# top.net
KiCad netlist of a schematic drawn in Altium Designer
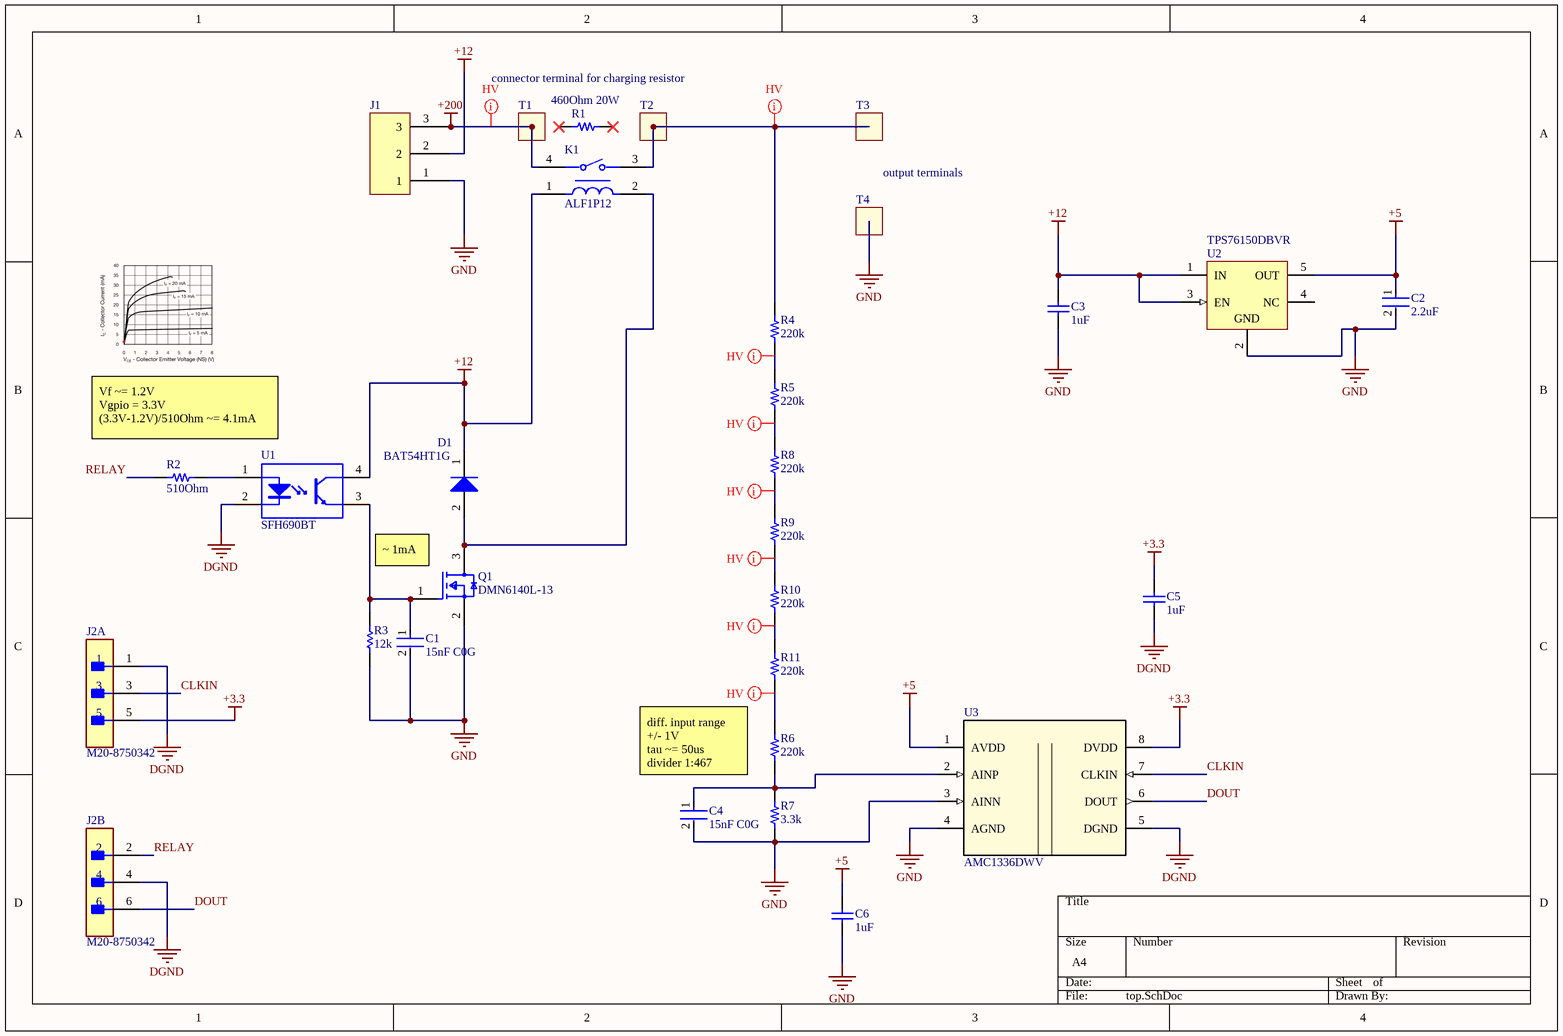
[diagram p0: top.SchDoc]

(export (version "E")
  (design (tool "Eeschema 10.0.6"))
  (components
    (comp (ref "C1")
      (value "15nF C0G")
      (footprint "FP-C0603C-CF-MFG")
      (description "C0603 15,000 pF C0G 30ppm/°C 20.00% 25 V")
      (fields
        (field (name "MANUFACTURER PART NUMBER") "C0603C153M3GACTU")
        (field (name "MANUFACTURER") "KEMET")
      )
      (libsource (lib "Altium Content Vault") (part "b4654b650e69147ec39a6b967a45e02"))
    )
    (comp (ref "C2")
      (value "2.2uF")
      (footprint "FP-GRM188-0_1-e0_2_0_5-MFG")
      (description "Chip Multilayer Ceramic Capacitors for General Purpose, 0603, 2.2uF, X7R, 15%, 10%, 10V")
      (fields (field (name "VOLTAGE") "10V") (field (name "TOLERANCE") "10%"))
      (libsource (lib "Altium Content Vault") (part "11868f565c42a9108669ba33697ecf6"))
    )
    (comp (ref "C3")
      (value "1uF")
      (footprint "CAPC1608X87X35LL15T15")
      (fields (field (name "PART NUMBER") "C0603C105K3RACTU") (field (name "MANUFACTURER") "Kemet"))
      (libsource (lib "Altium Content Vault") (part "CAP"))
    )
    (comp (ref "C4")
      (value "15nF C0G")
      (footprint "FP-C0603C-CF-MFG")
      (description "C0603 15,000 pF C0G 30ppm/°C 20.00% 25 V")
      (fields
        (field (name "MANUFACTURER PART NUMBER") "C0603C153M3GACTU")
        (field (name "MANUFACTURER") "KEMET")
      )
      (libsource (lib "Altium Content Vault") (part "b4654b650e69147ec39a6b967a45e02"))
    )
    (comp (ref "C5")
      (value "1uF")
      (footprint "CAPC1608X87X35LL15T15")
      (fields (field (name "PART NUMBER") "C0603C105K3RACTU") (field (name "MANUFACTURER") "Kemet"))
      (libsource (lib "Altium Content Vault") (part "CAP"))
    )
    (comp (ref "C6")
      (value "1uF")
      (footprint "CAPC1608X87X35LL15T15")
      (fields (field (name "PART NUMBER") "C0603C105K3RACTU") (field (name "MANUFACTURER") "Kemet"))
      (libsource (lib "Altium Content Vault") (part "CAP"))
    )
    (comp (ref "D1")
      (value "BAT54HT1G")
      (footprint "ONSC-SOD-323-2-477-02_V")
      (description "Schottky Barrier Diode, 2-Pin SOD-323, Pb-Free, Tape and Reel")
      (fields (field (name "MANUFACTURER") "On Semiconductor"))
      (libsource (lib "Altium Content Vault") (part "ONSC-D-K1A2-2"))
    )
    (comp (ref "J1")
      (value "20A Socket 3Pin")
      (footprint "weidmuller_3p_20A")
      (libsource (lib "coil_driver_lib") (part "wuerth_connector_straight_30_20A_691311500103"))
    )
    (comp (ref "J2")
      (value "M20-8750342")
      (footprint "FP-M20-8750342-MFG")
      (description "CONN HEADER SMD 6POS 2.54MM")
      (libsource (lib "Altium Content Vault") (part "2654a11fb13586ecb194516b1c997bc"))
    )
    (comp (ref "K1")
      (value "ALF1P12")
      (footprint "FP-ALF1P12-MFG")
      (description "RELAY GEN PURPOSE SPST 20A 12V")
      (libsource (lib "Altium Content Vault") (part "80a4a68f91ad243dcae29d2df2c1dea"))
    )
    (comp (ref "Q1")
      (value "DMN6140L-13")
      (footprint "FP-SOT23-MFG")
      (description "MOSFET N-CH 60V 1.6A SOT23")
      (fields
        (field (name "OCTOPART") "https://octopart.com/dmn6140l-13-diodes+inc.-38898616")
        (field (name "MANUFACTURER") "Diodes Inc.")
      )
      (libsource (lib "Altium Content Vault") (part "0a9ea7c96deaaede766a5b531c28de0"))
    )
    (comp (ref "R1")
      (value "460Ohm 20W")
      (description "SMT Resistor")
      (libsource (lib "SCH - PASSIVES - RESISTOR") (part "Resistor"))
    )
    (comp (ref "R2")
      (value "510Ohm")
      (footprint "RES 0603_1608")
      (description "SMT Resistor")
      (libsource (lib "SCH - PASSIVES - RESISTOR") (part "Resistor"))
    )
    (comp (ref "R3")
      (value "12k")
      (footprint "RES 0805_2012")
      (description "Resistor")
      (fields (field (name "PUBLISHER") "Altium Limited"))
      (libsource (lib "Miscellaneous Devices") (part "Res1"))
    )
    (comp (ref "R4")
      (value "220k")
      (footprint "RES 0603_1608 RF")
      (description "SMT Resistor")
      (libsource (lib "SCH - PASSIVES - RESISTOR") (part "Resistor"))
    )
    (comp (ref "R5")
      (value "220k")
      (footprint "RES 0603_1608 RF")
      (description "SMT Resistor")
      (libsource (lib "SCH - PASSIVES - RESISTOR") (part "Resistor"))
    )
    (comp (ref "R6")
      (value "220k")
      (footprint "RES 0603_1608 RF")
      (description "SMT Resistor")
      (libsource (lib "SCH - PASSIVES - RESISTOR") (part "Resistor"))
    )
    (comp (ref "R7")
      (value "3.3k")
      (footprint "RES 0603_1608")
      (description "SMT Resistor")
      (libsource (lib "SCH - PASSIVES - RESISTOR") (part "Resistor"))
    )
    (comp (ref "R8")
      (value "220k")
      (footprint "RES 0603_1608 RF")
      (description "SMT Resistor")
      (libsource (lib "SCH - PASSIVES - RESISTOR") (part "Resistor"))
    )
    (comp (ref "R9")
      (value "220k")
      (footprint "RES 0603_1608 RF")
      (description "SMT Resistor")
      (libsource (lib "SCH - PASSIVES - RESISTOR") (part "Resistor"))
    )
    (comp (ref "R10")
      (value "220k")
      (footprint "RES 0603_1608 RF")
      (description "SMT Resistor")
      (libsource (lib "SCH - PASSIVES - RESISTOR") (part "Resistor"))
    )
    (comp (ref "R11")
      (value "220k")
      (footprint "RES 0603_1608 RF")
      (description "SMT Resistor")
      (libsource (lib "SCH - PASSIVES - RESISTOR") (part "Resistor"))
    )
    (comp (ref "T1")
      (value "pwr_connector_quick")
      (footprint "pcb_quick_power_connector")
      (libsource (lib "coil_driver_lib") (part "pwr_connector_quick"))
    )
    (comp (ref "T2")
      (value "pwr_connector_quick")
      (footprint "pcb_quick_power_connector")
      (libsource (lib "coil_driver_lib") (part "pwr_connector_quick"))
    )
    (comp (ref "T3")
      (value "pwr_connector_quick")
      (footprint "pcb_quick_power_connector")
      (libsource (lib "coil_driver_lib") (part "pwr_connector_quick"))
    )
    (comp (ref "T4")
      (value "pwr_connector_quick")
      (footprint "pcb_quick_power_connector")
      (libsource (lib "coil_driver_lib") (part "pwr_connector_quick"))
    )
    (comp (ref "U1")
      (value "SFH690BT")
      (footprint "VISH-SOP-4_A_V")
      (description "Optocoupler Phototransistor Output, 6 V, 50 mA, -55 to 100 degC, 4-Pin SOIC, RoHS, Tape and Reel")
      (fields (field (name "MANUFACTURER") "Vishay"))
      (libsource (lib "Altium Content Vault") (part "OPTO-AKEC-4"))
    )
    (comp (ref "U2")
      (value "TPS76150DBVR")
      (footprint "DBV0005A_M")
      (fields (field (name "MANUFACTURER") "Texas Instruments"))
      (libsource (lib "Altium Content Vault") (part "TI-TXX7XXXX-5"))
    )
    (comp (ref "U3")
      (value "AMC1336DWV")
      (footprint "AMC1336")
      (description "&plusmn;1-V input, precision voltage sensing reinforced isolated modulator 8-SOIC -40 to 125")
      (fields (field (name "COPYRIGHT") "Copyright (C) 2025 Ultra Librarian. All rights reserved."))
      (libsource (lib "AMC1336DWV") (part "AMC1336DWV"))
    )
  )
  (nets
    (net (code "1") (name "+3.3") (class "Default")
      (node (ref "C5") (pin "2") (pinfunction "2_2") (pintype "passive"))
      (node (ref "J2") (pin "5") (pinfunction "5_5") (pintype "passive"))
      (node (ref "U3") (pin "8") (pinfunction "DVDD_8") (pintype "power_in"))
    )
    (net (code "2") (name "+5") (class "Default")
      (node (ref "C2") (pin "1") (pinfunction "1_1") (pintype "passive"))
      (node (ref "C6") (pin "2") (pinfunction "2_2") (pintype "passive"))
      (node (ref "U2") (pin "5") (pinfunction "OUT_5") (pintype "power_in"))
      (node (ref "U3") (pin "1") (pinfunction "AVDD_1") (pintype "power_in"))
    )
    (net (code "3") (name "+12") (class "Default")
      (node (ref "C3") (pin "2") (pinfunction "2_2") (pintype "passive"))
      (node (ref "D1") (pin "1") (pinfunction "K_1") (pintype "passive"))
      (node (ref "J1") (pin "2") (pinfunction "2_2") (pintype "passive"))
      (node (ref "K1") (pin "1") (pinfunction "1_1") (pintype "passive"))
      (node (ref "U1") (pin "4") (pinfunction "COLLECTOR_4") (pintype "passive"))
      (node (ref "U2") (pin "1") (pinfunction "IN_1") (pintype "power_in"))
      (node (ref "U2") (pin "3") (pinfunction "EN_3") (pintype "input"))
    )
    (net (code "4") (name "+200") (class "Default")
      (node (ref "J1") (pin "3") (pinfunction "3_3") (pintype "passive"))
      (node (ref "K1") (pin "4") (pinfunction "COM_4") (pintype "passive"))
      (node (ref "T1") (pin "1") (pinfunction "1_1") (pintype "passive"))
    )
    (net (code "5") (name "/CLKIN") (class "Default")
      (node (ref "J2") (pin "3") (pinfunction "3_3") (pintype "passive"))
      (node (ref "U3") (pin "7") (pinfunction "CLKIN_7") (pintype "input"))
    )
    (net (code "6") (name "/DOUT") (class "Default")
      (node (ref "J2") (pin "6") (pinfunction "6_6") (pintype "passive"))
      (node (ref "U3") (pin "6") (pinfunction "DOUT_6") (pintype "output"))
    )
    (net (code "7") (name "/RELAY") (class "Default")
      (node (ref "J2") (pin "2") (pinfunction "2_2") (pintype "passive"))
      (node (ref "R2") (pin "1") (pinfunction "1_1") (pintype "passive"))
    )
    (net (code "8") (name "DGND") (class "Default")
      (node (ref "C5") (pin "1") (pinfunction "1_1") (pintype "passive"))
      (node (ref "J2") (pin "1") (pinfunction "1_1") (pintype "passive"))
      (node (ref "J2") (pin "4") (pinfunction "4_4") (pintype "passive"))
      (node (ref "U1") (pin "2") (pinfunction "CATHODE_2") (pintype "passive"))
      (node (ref "U3") (pin "5") (pinfunction "DGND_5") (pintype "power_in"))
    )
    (net (code "9") (name "GND") (class "Default")
      (node (ref "C1") (pin "2") (pinfunction "2_2") (pintype "passive"))
      (node (ref "C2") (pin "2") (pinfunction "2_2") (pintype "passive"))
      (node (ref "C3") (pin "1") (pinfunction "1_1") (pintype "passive"))
      (node (ref "C4") (pin "2") (pinfunction "2_2") (pintype "passive"))
      (node (ref "C6") (pin "1") (pinfunction "1_1") (pintype "passive"))
      (node (ref "J1") (pin "1") (pinfunction "1_1") (pintype "passive"))
      (node (ref "Q1") (pin "2") (pinfunction "S_2") (pintype "passive"))
      (node (ref "R3") (pin "1") (pinfunction "1_1") (pintype "passive"))
      (node (ref "R7") (pin "1") (pinfunction "1_1") (pintype "passive"))
      (node (ref "T4") (pin "1") (pinfunction "1_1") (pintype "passive"))
      (node (ref "U2") (pin "2") (pinfunction "GND_2") (pintype "power_in"))
      (node (ref "U3") (pin "3") (pinfunction "AINN_3") (pintype "input"))
      (node (ref "U3") (pin "4") (pinfunction "AGND_4") (pintype "power_in"))
    )
    (net (code "10") (name "Net-(D1-A)") (class "Default")
      (node (ref "D1") (pin "2") (pinfunction "A_2") (pintype "passive"))
      (node (ref "K1") (pin "2") (pinfunction "2_2") (pintype "passive"))
      (node (ref "Q1") (pin "3") (pinfunction "D_3") (pintype "passive"))
    )
    (net (code "11") (name "Net-(K1-NO)") (class "Default")
      (node (ref "K1") (pin "3") (pinfunction "NO_3") (pintype "passive"))
      (node (ref "R4") (pin "2") (pinfunction "2_2") (pintype "passive"))
      (node (ref "T2") (pin "1") (pinfunction "1_1") (pintype "passive"))
      (node (ref "T3") (pin "1") (pinfunction "1_1") (pintype "passive"))
    )
    (net (code "12") (name "Net-(Q1-G)") (class "Default")
      (node (ref "C1") (pin "1") (pinfunction "1_1") (pintype "passive"))
      (node (ref "Q1") (pin "1") (pinfunction "G_1") (pintype "passive"))
      (node (ref "R3") (pin "2") (pinfunction "2_2") (pintype "passive"))
      (node (ref "U1") (pin "3") (pinfunction "EMITTER_3") (pintype "passive"))
    )
    (net (code "13") (name "Net-(R4-Pad1)") (class "Default")
      (node (ref "R4") (pin "1") (pinfunction "1_1") (pintype "passive"))
      (node (ref "R5") (pin "2") (pinfunction "2_2") (pintype "passive"))
    )
    (net (code "14") (name "Net-(R5-Pad1)") (class "Default")
      (node (ref "R5") (pin "1") (pinfunction "1_1") (pintype "passive"))
      (node (ref "R8") (pin "2") (pinfunction "2_2") (pintype "passive"))
    )
    (net (code "15") (name "Net-(R8-Pad1)") (class "Default")
      (node (ref "R8") (pin "1") (pinfunction "1_1") (pintype "passive"))
      (node (ref "R9") (pin "2") (pinfunction "2_2") (pintype "passive"))
    )
    (net (code "16") (name "Net-(R10-Pad1)") (class "Default")
      (node (ref "R10") (pin "1") (pinfunction "1_1") (pintype "passive"))
      (node (ref "R11") (pin "2") (pinfunction "2_2") (pintype "passive"))
    )
    (net (code "17") (name "Net-(R10-Pad2)") (class "Default")
      (node (ref "R10") (pin "2") (pinfunction "2_2") (pintype "passive"))
      (node (ref "R9") (pin "1") (pinfunction "1_1") (pintype "passive"))
    )
    (net (code "18") (name "Net-(R11-Pad1)") (class "Default")
      (node (ref "R11") (pin "1") (pinfunction "1_1") (pintype "passive"))
      (node (ref "R6") (pin "2") (pinfunction "2_2") (pintype "passive"))
    )
    (net (code "19") (name "Net-(U1-ANODE)") (class "Default")
      (node (ref "R2") (pin "2") (pinfunction "2_2") (pintype "passive"))
      (node (ref "U1") (pin "1") (pinfunction "ANODE_1") (pintype "passive"))
    )
    (net (code "20") (name "Net-(U3-AINP)") (class "Default")
      (node (ref "C4") (pin "1") (pinfunction "1_1") (pintype "passive"))
      (node (ref "R6") (pin "1") (pinfunction "1_1") (pintype "passive"))
      (node (ref "R7") (pin "2") (pinfunction "2_2") (pintype "passive"))
      (node (ref "U3") (pin "2") (pinfunction "AINP_2") (pintype "input"))
    )
    (net (code "21") (name "unconnected-(R1-Pad1)") (class "Default")
      (node (ref "R1") (pin "1") (pinfunction "1_1") (pintype "passive+no_connect"))
    )
    (net (code "22") (name "unconnected-(R1-Pad2)") (class "Default")
      (node (ref "R1") (pin "2") (pinfunction "2_2") (pintype "passive+no_connect"))
    )
    (net (code "23") (name "unconnected-(U2-NC-Pad4)") (class "Default")
      (node (ref "U2") (pin "4") (pinfunction "NC_4") (pintype "passive"))
    )
  )
)
